# DisplayPort_Connector.net
KiCad netlist of a schematic drawn in Altium Designer
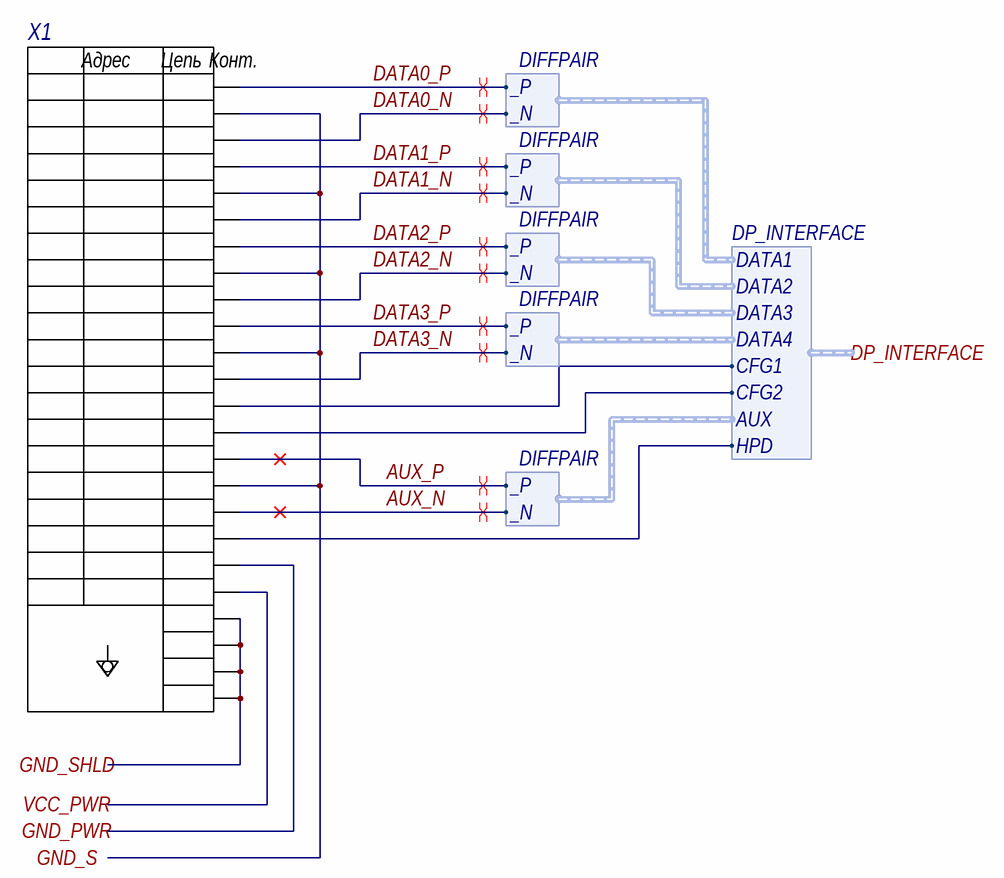
[diagram p0: DisplayPort Connector.SchDoc]

(export (version "E")
  (design (tool "Eeschema 10.0.6"))
  (components
    (comp (ref "X1")
      (value "472720024")
      (footprint "MOLX-472720024_V")
      (fields (field (name "MANUFACTURER") "Molex"))
      (libsource (lib "MiniPC DB") (part "DISP_PORT_SOED"))
    )
  )
  (nets
    (net (code "3") (name "/AUX_N") (class "Default")
      (node (ref "X1") (pin "17") (pinfunction "17_17") (pintype "passive"))
    )
    (net (code "4") (name "/AUX_P") (class "Default")
      (node (ref "X1") (pin "15") (pinfunction "15_15") (pintype "passive"))
    )
    (net (code "5") (name "/CFG1") (class "Default")
      (node (ref "X1") (pin "13") (pinfunction "13_13") (pintype "passive"))
    )
    (net (code "6") (name "/CFG2") (class "Default")
      (node (ref "X1") (pin "14") (pinfunction "14_14") (pintype "passive"))
    )
    (net (code "7") (name "/DATA0_N") (class "Default")
      (node (ref "X1") (pin "3") (pinfunction "3_3") (pintype "passive"))
    )
    (net (code "8") (name "/DATA0_P") (class "Default")
      (node (ref "X1") (pin "1") (pinfunction "1_1") (pintype "passive"))
    )
    (net (code "9") (name "/DATA1_N") (class "Default")
      (node (ref "X1") (pin "6") (pinfunction "6_6") (pintype "passive"))
    )
    (net (code "10") (name "/DATA1_P") (class "Default")
      (node (ref "X1") (pin "4") (pinfunction "4_4") (pintype "passive"))
    )
    (net (code "11") (name "/DATA2_N") (class "Default")
      (node (ref "X1") (pin "9") (pinfunction "9_9") (pintype "passive"))
    )
    (net (code "12") (name "/DATA2_P") (class "Default")
      (node (ref "X1") (pin "7") (pinfunction "7_7") (pintype "passive"))
    )
    (net (code "13") (name "/DATA3_N") (class "Default")
      (node (ref "X1") (pin "12") (pinfunction "12_12") (pintype "passive"))
    )
    (net (code "14") (name "/DATA3_P") (class "Default")
      (node (ref "X1") (pin "10") (pinfunction "10_10") (pintype "passive"))
    )
    (net (code "15") (name "/GND_PWR") (class "Default")
      (node (ref "X1") (pin "19") (pinfunction "19_19") (pintype "passive"))
    )
    (net (code "16") (name "/GND_S") (class "Default")
      (node (ref "X1") (pin "11") (pinfunction "11_11") (pintype "passive"))
      (node (ref "X1") (pin "16") (pinfunction "16_16") (pintype "passive"))
      (node (ref "X1") (pin "2") (pinfunction "2_2") (pintype "passive"))
      (node (ref "X1") (pin "5") (pinfunction "5_5") (pintype "passive"))
      (node (ref "X1") (pin "8") (pinfunction "8_8") (pintype "passive"))
    )
    (net (code "17") (name "/GND_SHLD") (class "Default")
      (node (ref "X1") (pin "21") (pinfunction "SHLD1_21") (pintype "passive"))
      (node (ref "X1") (pin "22") (pinfunction "SHLD2_22") (pintype "passive"))
      (node (ref "X1") (pin "23") (pinfunction "SHLD3_23") (pintype "passive"))
      (node (ref "X1") (pin "24") (pinfunction "SHLD4_24") (pintype "passive"))
    )
    (net (code "18") (name "/HPD") (class "Default")
      (node (ref "X1") (pin "18") (pinfunction "18_18") (pintype "passive"))
    )
    (net (code "19") (name "/VCC_PWR") (class "Default")
      (node (ref "X1") (pin "20") (pinfunction "20_20") (pintype "passive"))
    )
  )
)
